# 11_-_Power_Input_and_Regulators.net
KiCad netlist of a schematic drawn in Altium Designer
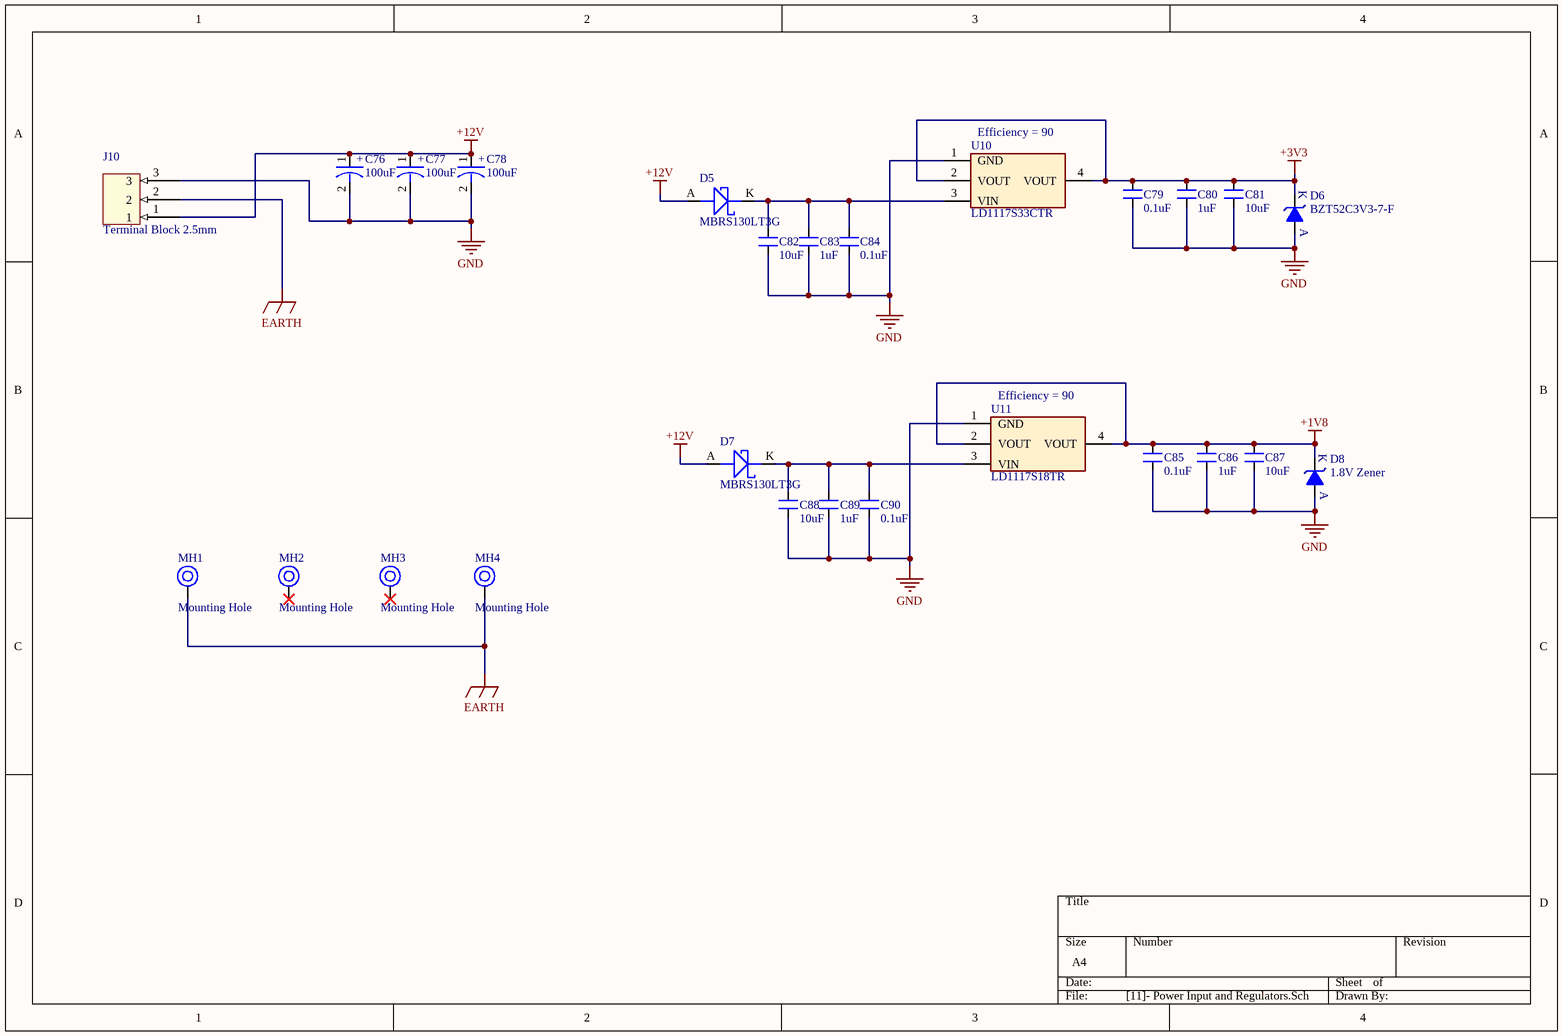
[diagram p0: [11]- Power Input and Regulators.SchDoc]

(export (version "E")
  (design (tool "Eeschema 10.0.6"))
  (components
    (comp (ref "C76")
      (value "100uF")
      (footprint "ACAP_P305_D393_H393_RAD")
      (description "100µF 50V Aluminum Polymer Capacitor Radial, Can - SMD 28mOhm 4000 Hrs @ 125°C")
      (fields
        (field (name "MANUFACTURER") "Nichicon")
        (field (name "MANUFACTURER PART NUMBER") "GYA1H101MCQ1GS")
      )
      (libsource (lib "ESTEEMPCBLIB") (part "CAP-P_100uF-50V-20%-RAD"))
    )
    (comp (ref "C77")
      (value "100uF")
      (footprint "ACAP_P305_D393_H393_RAD")
      (description "100µF 50V Aluminum Polymer Capacitor Radial, Can - SMD 28mOhm 4000 Hrs @ 125°C")
      (fields
        (field (name "MANUFACTURER") "Nichicon")
        (field (name "MANUFACTURER PART NUMBER") "GYA1H101MCQ1GS")
      )
      (libsource (lib "ESTEEMPCBLIB") (part "CAP-P_100uF-50V-20%-RAD"))
    )
    (comp (ref "C78")
      (value "100uF")
      (footprint "ACAP_P305_D393_H393_RAD")
      (description "100µF 50V Aluminum Polymer Capacitor Radial, Can - SMD 28mOhm 4000 Hrs @ 125°C")
      (fields
        (field (name "MANUFACTURER") "Nichicon")
        (field (name "MANUFACTURER PART NUMBER") "GYA1H101MCQ1GS")
      )
      (libsource (lib "ESTEEMPCBLIB") (part "CAP-P_100uF-50V-20%-RAD"))
    )
    (comp (ref "C79")
      (value "0.1uF")
      (footprint "CAP_0805")
      (description "0.1µF ±10% 50V Ceramic Capacitor X7R 0805 (2012 Metric)")
      (fields
        (field (name "MANUFACTURER") "Samsung")
        (field (name "MANUFACTURER PART NUMBER") "CL21B104KBCNNNC")
      )
      (libsource (lib "ESTEEMPCBLIB") (part "CAP_0.1uF-50V-10%-0805"))
    )
    (comp (ref "C80")
      (value "1uF")
      (footprint "CAP_0805")
      (description "1µF ±5% 50V Ceramic Capacitor X7R 0805 (2012 Metric)")
      (fields
        (field (name "MANUFACTURER") "Samsung")
        (field (name "MANUFACTURER PART NUMBER") "CC0805JKX7R9BB105")
      )
      (libsource (lib "ESTEEMPCBLIB") (part "CAP_1uF-50V-5%-0805"))
    )
    (comp (ref "C81")
      (value "10uF")
      (footprint "CAP_1206")
      (description "10µF ±10% 50V Ceramic Capacitor X7R 1206 (3216 Metric)")
      (fields
        (field (name "MANUFACTURER") "KEMET")
        (field (name "MANUFACTURER PART NUMBER") "CL31B106KBHNNNE")
      )
      (libsource (lib "ESTEEMPCBLIB") (part "CAP_10uF-50V-10%-1206"))
    )
    (comp (ref "C82")
      (value "10uF")
      (footprint "CAP_1206")
      (description "10µF ±10% 50V Ceramic Capacitor X7R 1206 (3216 Metric)")
      (fields
        (field (name "MANUFACTURER") "KEMET")
        (field (name "MANUFACTURER PART NUMBER") "CL31B106KBHNNNE")
      )
      (libsource (lib "ESTEEMPCBLIB") (part "CAP_10uF-50V-10%-1206"))
    )
    (comp (ref "C83")
      (value "1uF")
      (footprint "CAP_0805")
      (description "1µF ±5% 50V Ceramic Capacitor X7R 0805 (2012 Metric)")
      (fields
        (field (name "MANUFACTURER") "Samsung")
        (field (name "MANUFACTURER PART NUMBER") "CC0805JKX7R9BB105")
      )
      (libsource (lib "ESTEEMPCBLIB") (part "CAP_1uF-50V-5%-0805"))
    )
    (comp (ref "C84")
      (value "0.1uF")
      (footprint "CAP_0805")
      (description "0.1µF ±10% 50V Ceramic Capacitor X7R 0805 (2012 Metric)")
      (fields
        (field (name "MANUFACTURER") "Samsung")
        (field (name "MANUFACTURER PART NUMBER") "CL21B104KBCNNNC")
      )
      (libsource (lib "ESTEEMPCBLIB") (part "CAP_0.1uF-50V-10%-0805"))
    )
    (comp (ref "C85")
      (value "0.1uF")
      (footprint "CAP_0805")
      (description "0.1µF ±10% 50V Ceramic Capacitor X7R 0805 (2012 Metric)")
      (fields
        (field (name "MANUFACTURER") "Samsung")
        (field (name "MANUFACTURER PART NUMBER") "CL21B104KBCNNNC")
      )
      (libsource (lib "ESTEEMPCBLIB") (part "CAP_0.1uF-50V-10%-0805"))
    )
    (comp (ref "C86")
      (value "1uF")
      (footprint "CAP_0805")
      (description "1µF ±5% 50V Ceramic Capacitor X7R 0805 (2012 Metric)")
      (fields
        (field (name "MANUFACTURER") "Samsung")
        (field (name "MANUFACTURER PART NUMBER") "CC0805JKX7R9BB105")
      )
      (libsource (lib "ESTEEMPCBLIB") (part "CAP_1uF-50V-5%-0805"))
    )
    (comp (ref "C87")
      (value "10uF")
      (footprint "CAP_1206")
      (description "10µF ±10% 50V Ceramic Capacitor X7R 1206 (3216 Metric)")
      (fields
        (field (name "MANUFACTURER") "KEMET")
        (field (name "MANUFACTURER PART NUMBER") "CL31B106KBHNNNE")
      )
      (libsource (lib "ESTEEMPCBLIB") (part "CAP_10uF-50V-10%-1206"))
    )
    (comp (ref "C88")
      (value "10uF")
      (footprint "CAP_1206")
      (description "10µF ±10% 50V Ceramic Capacitor X7R 1206 (3216 Metric)")
      (fields
        (field (name "MANUFACTURER") "KEMET")
        (field (name "MANUFACTURER PART NUMBER") "CL31B106KBHNNNE")
      )
      (libsource (lib "ESTEEMPCBLIB") (part "CAP_10uF-50V-10%-1206"))
    )
    (comp (ref "C89")
      (value "1uF")
      (footprint "CAP_0805")
      (description "1µF ±5% 50V Ceramic Capacitor X7R 0805 (2012 Metric)")
      (fields
        (field (name "MANUFACTURER") "Samsung")
        (field (name "MANUFACTURER PART NUMBER") "CC0805JKX7R9BB105")
      )
      (libsource (lib "ESTEEMPCBLIB") (part "CAP_1uF-50V-5%-0805"))
    )
    (comp (ref "C90")
      (value "0.1uF")
      (footprint "CAP_0805")
      (description "0.1µF ±10% 50V Ceramic Capacitor X7R 0805 (2012 Metric)")
      (fields
        (field (name "MANUFACTURER") "Samsung")
        (field (name "MANUFACTURER PART NUMBER") "CL21B104KBCNNNC")
      )
      (libsource (lib "ESTEEMPCBLIB") (part "CAP_0.1uF-50V-10%-0805"))
    )
    (comp (ref "D5")
      (value "MBRS130LT3G")
      (footprint "DIO_SMB_DO-214AA")
      (description "Diode Schottky 30V 2A Surface Mount SMB")
      (fields (field (name "MANUFACTURER") "ON Semiconductor"))
      (libsource (lib "ESTEEMPCBLIB") (part "DIO-S_445mV-30V-2A-SMB"))
    )
    (comp (ref "D6")
      (value "BZT52C3V3-7-F")
      (footprint "DIO_SOD-123")
      (description "Zener Diode 3.3V 500mW ±6% Surface Mount SOD-123")
      (fields (field (name "MANUFACTURER") "Diodes Incorporated"))
      (libsource (lib "ESTEEMPCBLIB") (part "DIO-Z_3.3V-500mW-SOD123"))
    )
    (comp (ref "D7")
      (value "MBRS130LT3G")
      (footprint "DIO_SMB_DO-214AA")
      (description "Diode Schottky 30V 2A Surface Mount SMB")
      (fields (field (name "MANUFACTURER") "ON Semiconductor"))
      (libsource (lib "ESTEEMPCBLIB") (part "DIO-S_445mV-30V-2A-SMB"))
    )
    (comp (ref "D8")
      (value "1.8V Zener")
      (footprint "DIO_DO-213AB_SMD")
      (description "Zener Diode 1.8V 500mW ±5% Surface Mount DO-213AA")
      (libsource (lib "ESTEEMPCBLIB") (part "DIO-Z_1.8V-500mW-DO213AA"))
    )
    (comp (ref "J10")
      (value "Terminal Block 2.5mm")
      (footprint "CON3_100_TB_TH_ST")
      (description "3 Pins, 1 Row 2.54mm Pitch, straight Connector, male")
      (fields
        (field (name "MANUFACTURER PART NUMBER") "1725669")
        (field (name "MANUFACTURER") "Phoenix Contact")
      )
      (libsource (lib "ESTEEMPCBLIB") (part "CON-TB_3X1-100-ST-TH"))
    )
    (comp (ref "MH1")
      (value "Mounting Hole")
      (footprint "MOUNTING")
      (fields (field (name "MANUFACTURER PART NUMBER") "NA"))
      (libsource (lib "ESTEEMPCBLIB") (part "MH_3.5H_6D"))
    )
    (comp (ref "MH2")
      (value "Mounting Hole")
      (footprint "MOUNTING")
      (fields (field (name "MANUFACTURER PART NUMBER") "NA"))
      (libsource (lib "ESTEEMPCBLIB") (part "MH_3.5H_6D"))
    )
    (comp (ref "MH3")
      (value "Mounting Hole")
      (footprint "MOUNTING")
      (fields (field (name "MANUFACTURER PART NUMBER") "NA"))
      (libsource (lib "ESTEEMPCBLIB") (part "MH_3.5H_6D"))
    )
    (comp (ref "MH4")
      (value "Mounting Hole")
      (footprint "MOUNTING")
      (fields (field (name "MANUFACTURER PART NUMBER") "NA"))
      (libsource (lib "ESTEEMPCBLIB") (part "MH_3.5H_6D"))
    )
    (comp (ref "U10")
      (value "LD1117S33CTR")
      (footprint "SOT223_3")
      (description "Linear Voltage Regulator IC 1 Output 800mA SOT-223")
      (fields (field (name "MANUFACTURER") "STMicroelectronics"))
      (libsource (lib "ESTEEMPCBLIB") (part "REG_15V-3.3V-0.9A-12W-SOT223"))
    )
    (comp (ref "U11")
      (value "LD1117S18TR")
      (footprint "SOT223_3")
      (description "LDO Voltage Regulators 1.8V 0.8A Positive")
      (fields (field (name "MANUFACTURER") "STMicroelectronics"))
      (libsource (lib "ESTEEMPCBLIB") (part "REG_15V-1.8V-0.8A-1.4W-SOT223"))
    )
  )
  (nets
    (net (code "1") (name "+1V8") (class "Default")
      (node (ref "C85") (pin "2") (pinfunction "2_2") (pintype "passive"))
      (node (ref "C86") (pin "2") (pinfunction "2_2") (pintype "passive"))
      (node (ref "C87") (pin "2") (pinfunction "2_2") (pintype "passive"))
      (node (ref "D8") (pin "K") (pinfunction "K_K") (pintype "passive"))
      (node (ref "U11") (pin "2") (pinfunction "VOUT_2") (pintype "passive"))
      (node (ref "U11") (pin "4") (pinfunction "VOUT_4") (pintype "passive"))
    )
    (net (code "2") (name "+3V3") (class "Default")
      (node (ref "C79") (pin "2") (pinfunction "2_2") (pintype "passive"))
      (node (ref "C80") (pin "2") (pinfunction "2_2") (pintype "passive"))
      (node (ref "C81") (pin "2") (pinfunction "2_2") (pintype "passive"))
      (node (ref "D6") (pin "K") (pinfunction "K_K") (pintype "passive"))
      (node (ref "U10") (pin "2") (pinfunction "VOUT_2") (pintype "passive"))
      (node (ref "U10") (pin "4") (pinfunction "VOUT_4") (pintype "passive"))
    )
    (net (code "3") (name "+12V") (class "Default")
      (node (ref "C76") (pin "1") (pinfunction "1_1") (pintype "passive"))
      (node (ref "C77") (pin "1") (pinfunction "1_1") (pintype "passive"))
      (node (ref "C78") (pin "1") (pinfunction "1_1") (pintype "passive"))
      (node (ref "D5") (pin "A") (pinfunction "A_A") (pintype "passive"))
      (node (ref "D7") (pin "A") (pinfunction "A_A") (pintype "passive"))
      (node (ref "J10") (pin "1") (pinfunction "1_1") (pintype "input"))
    )
    (net (code "4") (name "EARTH") (class "Default")
      (node (ref "J10") (pin "2") (pinfunction "2_2") (pintype "input"))
      (node (ref "MH1") (pin "1") (pinfunction "1_1") (pintype "passive"))
      (node (ref "MH4") (pin "1") (pinfunction "1_1") (pintype "passive"))
    )
    (net (code "5") (name "GND") (class "Default")
      (node (ref "C76") (pin "2") (pinfunction "2_2") (pintype "passive"))
      (node (ref "C77") (pin "2") (pinfunction "2_2") (pintype "passive"))
      (node (ref "C78") (pin "2") (pinfunction "2_2") (pintype "passive"))
      (node (ref "C79") (pin "1") (pinfunction "1_1") (pintype "passive"))
      (node (ref "C80") (pin "1") (pinfunction "1_1") (pintype "passive"))
      (node (ref "C81") (pin "1") (pinfunction "1_1") (pintype "passive"))
      (node (ref "C82") (pin "1") (pinfunction "1_1") (pintype "passive"))
      (node (ref "C83") (pin "1") (pinfunction "1_1") (pintype "passive"))
      (node (ref "C84") (pin "1") (pinfunction "1_1") (pintype "passive"))
      (node (ref "C85") (pin "1") (pinfunction "1_1") (pintype "passive"))
      (node (ref "C86") (pin "1") (pinfunction "1_1") (pintype "passive"))
      (node (ref "C87") (pin "1") (pinfunction "1_1") (pintype "passive"))
      (node (ref "C88") (pin "1") (pinfunction "1_1") (pintype "passive"))
      (node (ref "C89") (pin "1") (pinfunction "1_1") (pintype "passive"))
      (node (ref "C90") (pin "1") (pinfunction "1_1") (pintype "passive"))
      (node (ref "D6") (pin "A") (pinfunction "A_A") (pintype "passive"))
      (node (ref "D8") (pin "A") (pinfunction "A_A") (pintype "passive"))
      (node (ref "J10") (pin "3") (pinfunction "3_3") (pintype "input"))
      (node (ref "U10") (pin "1") (pinfunction "GND_1") (pintype "passive"))
      (node (ref "U11") (pin "1") (pinfunction "GND_1") (pintype "passive"))
    )
    (net (code "6") (name "Net-(U10-VIN)") (class "Default")
      (node (ref "C82") (pin "2") (pinfunction "2_2") (pintype "passive"))
      (node (ref "C83") (pin "2") (pinfunction "2_2") (pintype "passive"))
      (node (ref "C84") (pin "2") (pinfunction "2_2") (pintype "passive"))
      (node (ref "D5") (pin "K") (pinfunction "K_K") (pintype "passive"))
      (node (ref "U10") (pin "3") (pinfunction "VIN_3") (pintype "passive"))
    )
    (net (code "7") (name "Net-(U11-VIN)") (class "Default")
      (node (ref "C88") (pin "2") (pinfunction "2_2") (pintype "passive"))
      (node (ref "C89") (pin "2") (pinfunction "2_2") (pintype "passive"))
      (node (ref "C90") (pin "2") (pinfunction "2_2") (pintype "passive"))
      (node (ref "D7") (pin "K") (pinfunction "K_K") (pintype "passive"))
      (node (ref "U11") (pin "3") (pinfunction "VIN_3") (pintype "passive"))
    )
    (net (code "8") (name "unconnected-(MH2-Pad1)") (class "Default")
      (node (ref "MH2") (pin "1") (pinfunction "1_1") (pintype "passive+no_connect"))
    )
    (net (code "9") (name "unconnected-(MH3-Pad1)") (class "Default")
      (node (ref "MH3") (pin "1") (pinfunction "1_1") (pintype "passive+no_connect"))
    )
  )
)
